# 0_iip_closure.net
KiCad netlist of a schematic drawn in Altium Designer
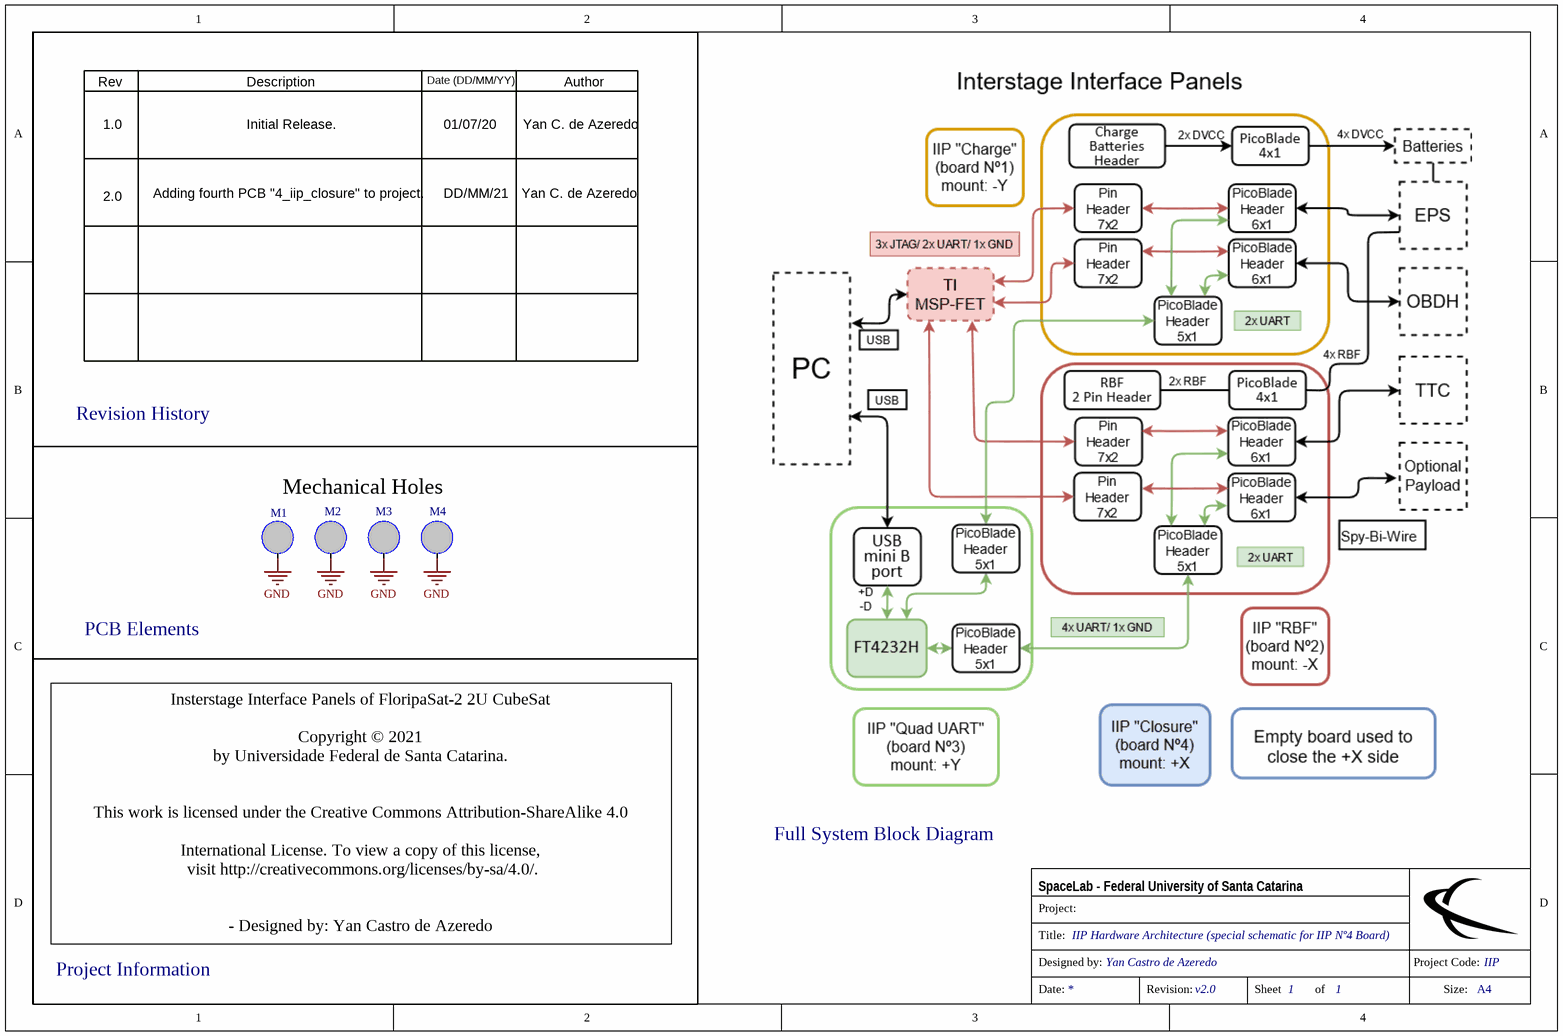
[diagram p0: 0_iip_closure.SchDoc]

(export (version "E")
  (design (tool "Eeschema 10.0.6"))
  (components
    (comp (ref "M1")
      (value "IB Mechanical Hole")
      (footprint "M3 hole (5.5mm pad)")
      (description "Mechanical Hole for FloripaSat-2 interface boards")
      (libsource (lib "iip") (part "IB Mechanical Hole"))
    )
    (comp (ref "M2")
      (value "IB Mechanical Hole")
      (footprint "M3 hole (5.5mm pad)")
      (description "Mechanical Hole for FloripaSat-2 interface boards")
      (libsource (lib "iip") (part "IB Mechanical Hole"))
    )
    (comp (ref "M3")
      (value "IB Mechanical Hole")
      (footprint "M3 hole (5.5mm pad)")
      (description "Mechanical Hole for FloripaSat-2 interface boards")
      (libsource (lib "iip") (part "IB Mechanical Hole"))
    )
    (comp (ref "M4")
      (value "IB Mechanical Hole")
      (footprint "M3 hole (5.5mm pad)")
      (description "Mechanical Hole for FloripaSat-2 interface boards")
      (libsource (lib "iip") (part "IB Mechanical Hole"))
    )
  )
  (nets
    (net (code "1") (name "GND") (class "Default")
      (node (ref "M1") (pin "0") (pinfunction "0_0") (pintype "passive"))
      (node (ref "M2") (pin "0") (pinfunction "0_0") (pintype "passive"))
      (node (ref "M3") (pin "0") (pinfunction "0_0") (pintype "passive"))
      (node (ref "M4") (pin "0") (pinfunction "0_0") (pintype "passive"))
    )
  )
)
